# moveWiFi.net
KiCad netlist of a schematic drawn in Altium Designer
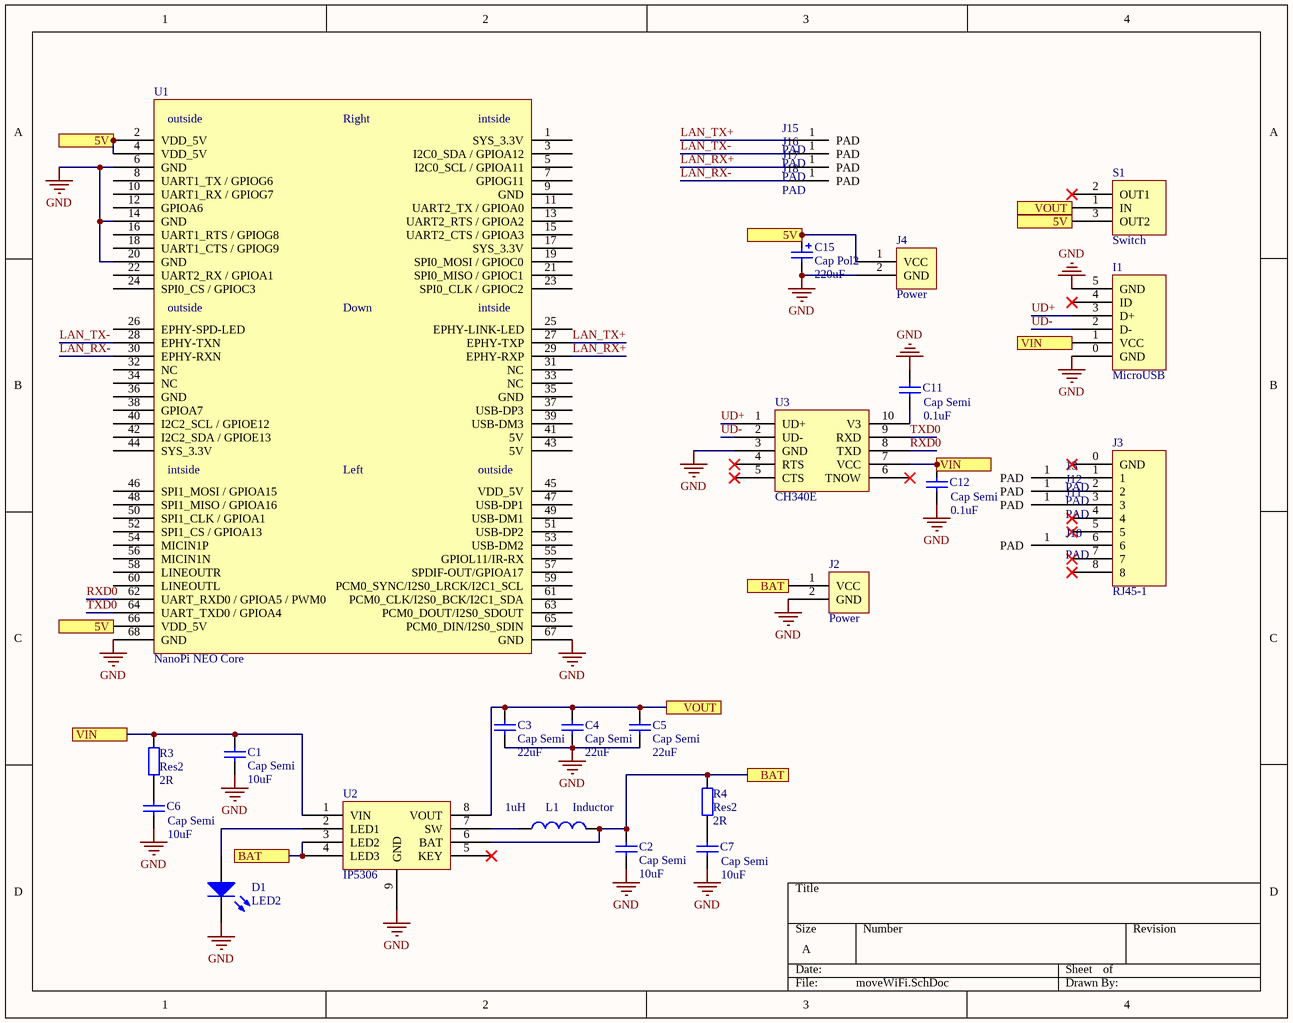
[diagram p0: moveWiFi.SchDoc]

(export (version "E")
  (design (tool "Eeschema 10.0.6"))
  (components
    (comp (ref "13") (value "PAD") (footprint "PAD") (libsource (lib "GavinPCBLib") (part "PAD")))
    (comp (ref "C1")
      (value "Cap Semi")
      (footprint "我的元件库01:C0805")
      (description "Capacitor (Semiconductor SIM Model)")
      (fields (field (name "ALTIUM_VALUE") "10uF") (field (name "PUBLISHER") "Altium Limited"))
      (libsource (lib "Miscellaneous Devices") (part "Cap Semi"))
    )
    (comp (ref "C2")
      (value "Cap Semi")
      (footprint "我的元件库01:C0805")
      (description "Capacitor (Semiconductor SIM Model)")
      (fields (field (name "ALTIUM_VALUE") "10uF") (field (name "PUBLISHER") "Altium Limited"))
      (libsource (lib "Miscellaneous Devices") (part "Cap Semi"))
    )
    (comp (ref "C3")
      (value "Cap Semi")
      (footprint "我的元件库01:C0805")
      (description "Capacitor (Semiconductor SIM Model)")
      (fields (field (name "ALTIUM_VALUE") "22uF") (field (name "PUBLISHER") "Altium Limited"))
      (libsource (lib "Miscellaneous Devices") (part "Cap Semi"))
    )
    (comp (ref "C4")
      (value "Cap Semi")
      (footprint "我的元件库01:C0805")
      (description "Capacitor (Semiconductor SIM Model)")
      (fields (field (name "ALTIUM_VALUE") "22uF") (field (name "PUBLISHER") "Altium Limited"))
      (libsource (lib "Miscellaneous Devices") (part "Cap Semi"))
    )
    (comp (ref "C5")
      (value "Cap Semi")
      (footprint "我的元件库01:C0805")
      (description "Capacitor (Semiconductor SIM Model)")
      (fields (field (name "ALTIUM_VALUE") "22uF") (field (name "PUBLISHER") "Altium Limited"))
      (libsource (lib "Miscellaneous Devices") (part "Cap Semi"))
    )
    (comp (ref "C6")
      (value "Cap Semi")
      (footprint "我的元件库01:C0805")
      (description "Capacitor (Semiconductor SIM Model)")
      (fields (field (name "ALTIUM_VALUE") "10uF") (field (name "PUBLISHER") "Altium Limited"))
      (libsource (lib "Miscellaneous Devices") (part "Cap Semi"))
    )
    (comp (ref "C7")
      (value "Cap Semi")
      (footprint "我的元件库01:C0805")
      (description "Capacitor (Semiconductor SIM Model)")
      (fields (field (name "ALTIUM_VALUE") "10uF") (field (name "PUBLISHER") "Altium Limited"))
      (libsource (lib "Miscellaneous Devices") (part "Cap Semi"))
    )
    (comp (ref "C11")
      (value "Cap Semi")
      (footprint "C0603")
      (description "Capacitor (Semiconductor SIM Model)")
      (fields (field (name "ALTIUM_VALUE") "0.1uF") (field (name "PUBLISHER") "Altium Limited"))
      (libsource (lib "Miscellaneous Devices") (part "Cap Semi"))
    )
    (comp (ref "C12")
      (value "Cap Semi")
      (footprint "C0603")
      (description "Capacitor (Semiconductor SIM Model)")
      (fields (field (name "ALTIUM_VALUE") "0.1uF") (field (name "PUBLISHER") "Altium Limited"))
      (libsource (lib "Miscellaneous Devices") (part "Cap Semi"))
    )
    (comp (ref "C15")
      (value "Cap Pol2")
      (footprint "C7343")
      (description "Polarized Capacitor (Axial)")
      (fields (field (name "ALTIUM_VALUE") "220uF") (field (name "PUBLISHER") "Altium Limited"))
      (libsource (lib "Miscellaneous Devices") (part "Cap Pol2"))
    )
    (comp (ref "D1")
      (value "LED2")
      (footprint "R0603")
      (description "Typical RED, GREEN, YELLOW, AMBER GaAs LED")
      (fields (field (name "PUBLISHER") "Altium Limited"))
      (libsource (lib "Miscellaneous Devices") (part "LED2"))
    )
    (comp (ref "I1")
      (value "MicroUSB")
      (footprint "MicroUSB")
      (libsource (lib "GavinPCBLib") (part "MicroUSB"))
    )
    (comp (ref "J2") (value "Power") (footprint "Power 2") (libsource (lib "GavinPCBLib") (part "Power")))
    (comp (ref "J3") (value "RJ45-1") (footprint "RG45-3") (libsource (lib "GavinPCBLib") (part "RJ45-3")))
    (comp (ref "J4") (value "Power") (footprint "Power 2") (libsource (lib "GavinPCBLib") (part "Power")))
    (comp (ref "J10") (value "PAD") (footprint "PAD") (libsource (lib "GavinPCBLib") (part "PAD")))
    (comp (ref "J11") (value "PAD") (footprint "PAD") (libsource (lib "GavinPCBLib") (part "PAD")))
    (comp (ref "J12") (value "PAD") (footprint "PAD") (libsource (lib "GavinPCBLib") (part "PAD")))
    (comp (ref "J15") (value "PAD") (footprint "PAD") (libsource (lib "GavinPCBLib") (part "PAD")))
    (comp (ref "J16") (value "PAD") (footprint "PAD") (libsource (lib "GavinPCBLib") (part "PAD")))
    (comp (ref "J17") (value "PAD") (footprint "PAD") (libsource (lib "GavinPCBLib") (part "PAD")))
    (comp (ref "J18") (value "PAD") (footprint "PAD") (libsource (lib "GavinPCBLib") (part "PAD")))
    (comp (ref "L1")
      (value "Inductor")
      (footprint "L0630")
      (fields (field (name "ALTIUM_VALUE") "1uH") (field (name "PUBLISHER") "Altium Limited"))
      (libsource (lib "Miscellaneous Devices") (part "Inductor"))
    )
    (comp (ref "R3")
      (value "Res2")
      (footprint "R0603")
      (description "Resistor")
      (fields (field (name "ALTIUM_VALUE") "2R") (field (name "PUBLISHER") "Altium Limited"))
      (libsource (lib "Miscellaneous Devices") (part "Res2"))
    )
    (comp (ref "R4")
      (value "Res2")
      (footprint "R0603")
      (description "Resistor")
      (fields (field (name "ALTIUM_VALUE") "2R") (field (name "PUBLISHER") "Altium Limited"))
      (libsource (lib "Miscellaneous Devices") (part "Res2"))
    )
    (comp (ref "S1") (value "Switch") (footprint "SwitchA") (libsource (lib "GavinPCBLib") (part "Switch")))
    (comp (ref "U1")
      (value "NanoPi NEO Core")
      (footprint "NanoPi_NEO_Core3")
      (libsource (lib "GavinPCBLib") (part "NanoPi_NEO_Core"))
    )
    (comp (ref "U2") (value "IP5306") (footprint "eSOP8") (libsource (lib "GavinPCBLib") (part "IP5306")))
    (comp (ref "U3") (value "CH340E") (footprint "MSOP-10") (libsource (lib "GavinPCBLib") (part "CH340E")))
  )
  (nets
    (net (code "1") (name "/5V") (class "Default")
      (node (ref "C15") (pin "1") (pinfunction "1_1") (pintype "passive"))
      (node (ref "J4") (pin "1") (pinfunction "VCC_1") (pintype "passive"))
      (node (ref "S1") (pin "3") (pinfunction "OUT2_3") (pintype "passive"))
      (node (ref "U1") (pin "2") (pinfunction "VDD_5V_2") (pintype "passive"))
      (node (ref "U1") (pin "4") (pinfunction "VDD_5V_4") (pintype "passive"))
      (node (ref "U1") (pin "66") (pinfunction "VDD_5V_66") (pintype "passive"))
    )
    (net (code "2") (name "/BAT") (class "Default")
      (node (ref "C2") (pin "2") (pinfunction "2_2") (pintype "passive"))
      (node (ref "J2") (pin "1") (pinfunction "VCC_1") (pintype "passive"))
      (node (ref "L1") (pin "2") (pinfunction "2_2") (pintype "passive"))
      (node (ref "R4") (pin "2") (pinfunction "2_2") (pintype "passive"))
      (node (ref "U2") (pin "3") (pinfunction "LED2_3") (pintype "passive"))
      (node (ref "U2") (pin "4") (pinfunction "LED3_4") (pintype "passive"))
      (node (ref "U2") (pin "6") (pinfunction "BAT_6") (pintype "passive"))
    )
    (net (code "3") (name "/LAN_RX+") (class "Default")
      (node (ref "J17") (pin "1") (pinfunction "PAD_1") (pintype "passive"))
      (node (ref "U1") (pin "29") (pinfunction "EPHY-RXP_29") (pintype "passive"))
    )
    (net (code "4") (name "/LAN_RX-") (class "Default")
      (node (ref "J18") (pin "1") (pinfunction "PAD_1") (pintype "passive"))
      (node (ref "U1") (pin "30") (pinfunction "EPHY-RXN_30") (pintype "passive"))
    )
    (net (code "5") (name "/LAN_TX+") (class "Default")
      (node (ref "J15") (pin "1") (pinfunction "PAD_1") (pintype "passive"))
      (node (ref "U1") (pin "27") (pinfunction "EPHY-TXP_27") (pintype "passive"))
    )
    (net (code "6") (name "/LAN_TX-") (class "Default")
      (node (ref "J16") (pin "1") (pinfunction "PAD_1") (pintype "passive"))
      (node (ref "U1") (pin "28") (pinfunction "EPHY-TXN_28") (pintype "passive"))
    )
    (net (code "7") (name "/RXD0") (class "Default")
      (node (ref "U1") (pin "62") (pinfunction "UART_RXD0_/_GPIOA5_/_PWM0_62") (pintype "passive"))
      (node (ref "U3") (pin "8") (pinfunction "TXD_8") (pintype "passive"))
    )
    (net (code "8") (name "/TXD0") (class "Default")
      (node (ref "U1") (pin "64") (pinfunction "UART_TXD0_/_GPIOA4_64") (pintype "passive"))
      (node (ref "U3") (pin "9") (pinfunction "RXD_9") (pintype "passive"))
    )
    (net (code "9") (name "/UD+") (class "Default")
      (node (ref "I1") (pin "3") (pinfunction "D+_3") (pintype "passive"))
      (node (ref "U3") (pin "1") (pinfunction "UD+_1") (pintype "passive"))
    )
    (net (code "10") (name "/UD-") (class "Default")
      (node (ref "I1") (pin "2") (pinfunction "D-_2") (pintype "passive"))
      (node (ref "U3") (pin "2") (pinfunction "UD-_2") (pintype "passive"))
    )
    (net (code "11") (name "/VIN") (class "Default")
      (node (ref "C1") (pin "2") (pinfunction "2_2") (pintype "passive"))
      (node (ref "C12") (pin "2") (pinfunction "2_2") (pintype "passive"))
      (node (ref "I1") (pin "1") (pinfunction "VCC_1") (pintype "passive"))
      (node (ref "R3") (pin "2") (pinfunction "2_2") (pintype "passive"))
      (node (ref "U2") (pin "1") (pinfunction "VIN_1") (pintype "passive"))
      (node (ref "U3") (pin "7") (pinfunction "VCC_7") (pintype "passive"))
    )
    (net (code "12") (name "/VOUT") (class "Default")
      (node (ref "C3") (pin "2") (pinfunction "2_2") (pintype "passive"))
      (node (ref "C4") (pin "2") (pinfunction "2_2") (pintype "passive"))
      (node (ref "C5") (pin "2") (pinfunction "2_2") (pintype "passive"))
      (node (ref "S1") (pin "1") (pinfunction "IN_1") (pintype "passive"))
      (node (ref "U2") (pin "8") (pinfunction "VOUT_8") (pintype "passive"))
    )
    (net (code "13") (name "GND") (class "Default")
      (node (ref "C1") (pin "1") (pinfunction "1_1") (pintype "passive"))
      (node (ref "C11") (pin "2") (pinfunction "2_2") (pintype "passive"))
      (node (ref "C12") (pin "1") (pinfunction "1_1") (pintype "passive"))
      (node (ref "C15") (pin "2") (pinfunction "2_2") (pintype "passive"))
      (node (ref "C2") (pin "1") (pinfunction "1_1") (pintype "passive"))
      (node (ref "C3") (pin "1") (pinfunction "1_1") (pintype "passive"))
      (node (ref "C4") (pin "1") (pinfunction "1_1") (pintype "passive"))
      (node (ref "C5") (pin "1") (pinfunction "1_1") (pintype "passive"))
      (node (ref "C6") (pin "1") (pinfunction "1_1") (pintype "passive"))
      (node (ref "C7") (pin "1") (pinfunction "1_1") (pintype "passive"))
      (node (ref "D1") (pin "2") (pinfunction "K_2") (pintype "passive"))
      (node (ref "I1") (pin "0") (pinfunction "GND_0") (pintype "passive"))
      (node (ref "I1") (pin "5") (pinfunction "GND_5") (pintype "passive"))
      (node (ref "J2") (pin "2") (pinfunction "GND_2") (pintype "passive"))
      (node (ref "J4") (pin "2") (pinfunction "GND_2") (pintype "passive"))
      (node (ref "U1") (pin "14") (pinfunction "GND_14") (pintype "passive"))
      (node (ref "U1") (pin "20") (pinfunction "GND_20") (pintype "passive"))
      (node (ref "U1") (pin "6") (pinfunction "GND_6") (pintype "passive"))
      (node (ref "U1") (pin "67") (pinfunction "GND_67") (pintype "passive"))
      (node (ref "U1") (pin "68") (pinfunction "GND_68") (pintype "passive"))
      (node (ref "U2") (pin "9") (pinfunction "GND_9") (pintype "passive"))
      (node (ref "U3") (pin "3") (pinfunction "GND_3") (pintype "passive"))
    )
    (net (code "14") (name "Net-(13-PAD)") (class "Default")
      (node (ref "13") (pin "1") (pinfunction "PAD_1") (pintype "passive"))
      (node (ref "J3") (pin "1") (pinfunction "1_1") (pintype "passive"))
    )
    (net (code "15") (name "Net-(C6-Pad2)") (class "Default")
      (node (ref "C6") (pin "2") (pinfunction "2_2") (pintype "passive"))
      (node (ref "R3") (pin "1") (pinfunction "1_1") (pintype "passive"))
    )
    (net (code "16") (name "Net-(C7-Pad2)") (class "Default")
      (node (ref "C7") (pin "2") (pinfunction "2_2") (pintype "passive"))
      (node (ref "R4") (pin "1") (pinfunction "1_1") (pintype "passive"))
    )
    (net (code "17") (name "Net-(D1-A)") (class "Default")
      (node (ref "D1") (pin "1") (pinfunction "A_1") (pintype "passive"))
      (node (ref "U2") (pin "2") (pinfunction "LED1_2") (pintype "passive"))
    )
    (net (code "18") (name "Net-(J10-PAD)") (class "Default")
      (node (ref "J10") (pin "1") (pinfunction "PAD_1") (pintype "passive"))
      (node (ref "J3") (pin "6") (pinfunction "6_6") (pintype "passive"))
    )
    (net (code "19") (name "Net-(J11-PAD)") (class "Default")
      (node (ref "J11") (pin "1") (pinfunction "PAD_1") (pintype "passive"))
      (node (ref "J3") (pin "3") (pinfunction "3_3") (pintype "passive"))
    )
    (net (code "20") (name "Net-(J12-PAD)") (class "Default")
      (node (ref "J12") (pin "1") (pinfunction "PAD_1") (pintype "passive"))
      (node (ref "J3") (pin "2") (pinfunction "2_2") (pintype "passive"))
    )
    (net (code "21") (name "Net-(U2-SW)") (class "Default")
      (node (ref "L1") (pin "1") (pinfunction "1_1") (pintype "passive"))
      (node (ref "U2") (pin "7") (pinfunction "SW_7") (pintype "passive"))
    )
    (net (code "22") (name "Net-(U3-V3)") (class "Default")
      (node (ref "C11") (pin "1") (pinfunction "1_1") (pintype "passive"))
      (node (ref "U3") (pin "10") (pinfunction "V3_10") (pintype "passive"))
    )
    (net (code "23") (name "unconnected-(I1-ID-Pad4)") (class "Default")
      (node (ref "I1") (pin "4") (pinfunction "ID_4") (pintype "passive+no_connect"))
    )
    (net (code "24") (name "unconnected-(J3-GND-Pad0)") (class "Default")
      (node (ref "J3") (pin "0") (pinfunction "GND_0") (pintype "passive+no_connect"))
    )
    (net (code "25") (name "unconnected-(J3-Pad4)") (class "Default")
      (node (ref "J3") (pin "4") (pinfunction "4_4") (pintype "passive+no_connect"))
    )
    (net (code "26") (name "unconnected-(J3-Pad5)") (class "Default")
      (node (ref "J3") (pin "5") (pinfunction "5_5") (pintype "passive+no_connect"))
    )
    (net (code "27") (name "unconnected-(J3-Pad7)") (class "Default")
      (node (ref "J3") (pin "7") (pinfunction "7_7") (pintype "passive+no_connect"))
    )
    (net (code "28") (name "unconnected-(J3-Pad8)") (class "Default")
      (node (ref "J3") (pin "8") (pinfunction "8_8") (pintype "passive+no_connect"))
    )
    (net (code "29") (name "unconnected-(S1-OUT1-Pad2)") (class "Default")
      (node (ref "S1") (pin "2") (pinfunction "OUT1_2") (pintype "passive+no_connect"))
    )
    (net (code "30") (name "unconnected-(U1-5V-Pad41)") (class "Default")
      (node (ref "U1") (pin "41") (pinfunction "5V_41") (pintype "passive"))
    )
    (net (code "31") (name "unconnected-(U1-5V-Pad43)") (class "Default")
      (node (ref "U1") (pin "43") (pinfunction "5V_43") (pintype "passive"))
    )
    (net (code "32") (name "unconnected-(U1-EPHY-LINK-LED-Pad25)") (class "Default")
      (node (ref "U1") (pin "25") (pinfunction "EPHY-LINK-LED_25") (pintype "passive"))
    )
    (net (code "33") (name "unconnected-(U1-EPHY-SPD-LED-Pad26)") (class "Default")
      (node (ref "U1") (pin "26") (pinfunction "EPHY-SPD-LED_26") (pintype "passive"))
    )
    (net (code "34") (name "unconnected-(U1-GND-Pad9)") (class "Default")
      (node (ref "U1") (pin "9") (pinfunction "GND_9") (pintype "passive"))
    )
    (net (code "35") (name "unconnected-(U1-GND-Pad35)") (class "Default")
      (node (ref "U1") (pin "35") (pinfunction "GND_35") (pintype "passive"))
    )
    (net (code "36") (name "unconnected-(U1-GND-Pad36)") (class "Default")
      (node (ref "U1") (pin "36") (pinfunction "GND_36") (pintype "passive"))
    )
    (net (code "37") (name "unconnected-(U1-GPIOA6-Pad12)") (class "Default")
      (node (ref "U1") (pin "12") (pinfunction "GPIOA6_12") (pintype "passive"))
    )
    (net (code "38") (name "unconnected-(U1-GPIOA7-Pad38)") (class "Default")
      (node (ref "U1") (pin "38") (pinfunction "GPIOA7_38") (pintype "passive"))
    )
    (net (code "39") (name "unconnected-(U1-GPIOG11-Pad7)") (class "Default")
      (node (ref "U1") (pin "7") (pinfunction "GPIOG11_7") (pintype "passive"))
    )
    (net (code "40") (name "unconnected-(U1-GPIOL11{slash}IR-RX-Pad55)") (class "Default")
      (node (ref "U1") (pin "55") (pinfunction "GPIOL11/IR-RX_55") (pintype "passive"))
    )
    (net (code "41") (name "unconnected-(U1-I2C0_SCL_{slash}_GPIOA11-Pad5)") (class "Default")
      (node (ref "U1") (pin "5") (pinfunction "I2C0_SCL_/_GPIOA11_5") (pintype "passive"))
    )
    (net (code "42") (name "unconnected-(U1-I2C0_SDA_{slash}_GPIOA12-Pad3)") (class "Default")
      (node (ref "U1") (pin "3") (pinfunction "I2C0_SDA_/_GPIOA12_3") (pintype "passive"))
    )
    (net (code "43") (name "unconnected-(U1-I2C2_SCL_{slash}_GPIOE12-Pad40)") (class "Default")
      (node (ref "U1") (pin "40") (pinfunction "I2C2_SCL_/_GPIOE12_40") (pintype "passive"))
    )
    (net (code "44") (name "unconnected-(U1-I2C2_SDA_{slash}_GPIOE13-Pad42)") (class "Default")
      (node (ref "U1") (pin "42") (pinfunction "I2C2_SDA_/_GPIOE13_42") (pintype "passive"))
    )
    (net (code "45") (name "unconnected-(U1-LINEOUTL-Pad60)") (class "Default")
      (node (ref "U1") (pin "60") (pinfunction "LINEOUTL_60") (pintype "passive"))
    )
    (net (code "46") (name "unconnected-(U1-LINEOUTR-Pad58)") (class "Default")
      (node (ref "U1") (pin "58") (pinfunction "LINEOUTR_58") (pintype "passive"))
    )
    (net (code "47") (name "unconnected-(U1-MICIN1N-Pad56)") (class "Default")
      (node (ref "U1") (pin "56") (pinfunction "MICIN1N_56") (pintype "passive"))
    )
    (net (code "48") (name "unconnected-(U1-MICIN1P-Pad54)") (class "Default")
      (node (ref "U1") (pin "54") (pinfunction "MICIN1P_54") (pintype "passive"))
    )
    (net (code "49") (name "unconnected-(U1-NC-Pad31)") (class "Default")
      (node (ref "U1") (pin "31") (pinfunction "NC_31") (pintype "passive"))
    )
    (net (code "50") (name "unconnected-(U1-NC-Pad32)") (class "Default")
      (node (ref "U1") (pin "32") (pinfunction "NC_32") (pintype "passive"))
    )
    (net (code "51") (name "unconnected-(U1-NC-Pad33)") (class "Default")
      (node (ref "U1") (pin "33") (pinfunction "NC_33") (pintype "passive"))
    )
    (net (code "52") (name "unconnected-(U1-NC-Pad34)") (class "Default")
      (node (ref "U1") (pin "34") (pinfunction "NC_34") (pintype "passive"))
    )
    (net (code "53") (name "unconnected-(U1-PCM0_CLK{slash}I2S0_BCK{slash}I2C1_SDA-Pad61)") (class "Default")
      (node (ref "U1") (pin "61") (pinfunction "PCM0_CLK/I2S0_BCK/I2C1_SDA_61") (pintype "passive"))
    )
    (net (code "54") (name "unconnected-(U1-PCM0_DIN{slash}I2S0_SDIN-Pad65)") (class "Default")
      (node (ref "U1") (pin "65") (pinfunction "PCM0_DIN/I2S0_SDIN_65") (pintype "passive"))
    )
    (net (code "55") (name "unconnected-(U1-PCM0_DOUT{slash}I2S0_SDOUT-Pad63)") (class "Default")
      (node (ref "U1") (pin "63") (pinfunction "PCM0_DOUT/I2S0_SDOUT_63") (pintype "passive"))
    )
    (net (code "56") (name "unconnected-(U1-PCM0_SYNC{slash}I2S0_LRCK{slash}I2C1_SCL-Pad59)") (class "Default")
      (node (ref "U1") (pin "59") (pinfunction "PCM0_SYNC/I2S0_LRCK/I2C1_SCL_59") (pintype "passive"))
    )
    (net (code "57") (name "unconnected-(U1-SPDIF-OUT{slash}GPIOA17-Pad57)") (class "Default")
      (node (ref "U1") (pin "57") (pinfunction "SPDIF-OUT/GPIOA17_57") (pintype "passive"))
    )
    (net (code "58") (name "unconnected-(U1-SPI0_CLK_{slash}_GPIOC2-Pad23)") (class "Default")
      (node (ref "U1") (pin "23") (pinfunction "SPI0_CLK_/_GPIOC2_23") (pintype "passive"))
    )
    (net (code "59") (name "unconnected-(U1-SPI0_CS_{slash}_GPIOC3-Pad24)") (class "Default")
      (node (ref "U1") (pin "24") (pinfunction "SPI0_CS_/_GPIOC3_24") (pintype "passive"))
    )
    (net (code "60") (name "unconnected-(U1-SPI0_MISO_{slash}_GPIOC1-Pad21)") (class "Default")
      (node (ref "U1") (pin "21") (pinfunction "SPI0_MISO_/_GPIOC1_21") (pintype "passive"))
    )
    (net (code "61") (name "unconnected-(U1-SPI0_MOSI_{slash}_GPIOC0-Pad19)") (class "Default")
      (node (ref "U1") (pin "19") (pinfunction "SPI0_MOSI_/_GPIOC0_19") (pintype "passive"))
    )
    (net (code "62") (name "unconnected-(U1-SPI1_CLK_{slash}_GPIOA1-Pad50)") (class "Default")
      (node (ref "U1") (pin "50") (pinfunction "SPI1_CLK_/_GPIOA1_50") (pintype "passive"))
    )
    (net (code "63") (name "unconnected-(U1-SPI1_CS_{slash}_GPIOA13-Pad52)") (class "Default")
      (node (ref "U1") (pin "52") (pinfunction "SPI1_CS_/_GPIOA13_52") (pintype "passive"))
    )
    (net (code "64") (name "unconnected-(U1-SPI1_MISO_{slash}_GPIOA16-Pad48)") (class "Default")
      (node (ref "U1") (pin "48") (pinfunction "SPI1_MISO_/_GPIOA16_48") (pintype "passive"))
    )
    (net (code "65") (name "unconnected-(U1-SPI1_MOSI_{slash}_GPIOA15-Pad46)") (class "Default")
      (node (ref "U1") (pin "46") (pinfunction "SPI1_MOSI_/_GPIOA15_46") (pintype "passive"))
    )
    (net (code "66") (name "unconnected-(U1-SYS_3.3V-Pad1)") (class "Default")
      (node (ref "U1") (pin "1") (pinfunction "SYS_3.3V_1") (pintype "passive"))
    )
    (net (code "67") (name "unconnected-(U1-SYS_3.3V-Pad17)") (class "Default")
      (node (ref "U1") (pin "17") (pinfunction "SYS_3.3V_17") (pintype "passive"))
    )
    (net (code "68") (name "unconnected-(U1-SYS_3.3V-Pad44)") (class "Default")
      (node (ref "U1") (pin "44") (pinfunction "SYS_3.3V_44") (pintype "passive"))
    )
    (net (code "69") (name "unconnected-(U1-UART1_CTS_{slash}_GPIOG9-Pad18)") (class "Default")
      (node (ref "U1") (pin "18") (pinfunction "UART1_CTS_/_GPIOG9_18") (pintype "passive"))
    )
    (net (code "70") (name "unconnected-(U1-UART1_RTS_{slash}_GPIOG8-Pad16)") (class "Default")
      (node (ref "U1") (pin "16") (pinfunction "UART1_RTS_/_GPIOG8_16") (pintype "passive"))
    )
    (net (code "71") (name "unconnected-(U1-UART1_RX_{slash}_GPIOG7-Pad10)") (class "Default")
      (node (ref "U1") (pin "10") (pinfunction "UART1_RX_/_GPIOG7_10") (pintype "passive"))
    )
    (net (code "72") (name "unconnected-(U1-UART1_TX_{slash}_GPIOG6-Pad8)") (class "Default")
      (node (ref "U1") (pin "8") (pinfunction "UART1_TX_/_GPIOG6_8") (pintype "passive"))
    )
    (net (code "73") (name "unconnected-(U1-UART2_CTS_{slash}_GPIOA3-Pad15)") (class "Default")
      (node (ref "U1") (pin "15") (pinfunction "UART2_CTS_/_GPIOA3_15") (pintype "passive"))
    )
    (net (code "74") (name "unconnected-(U1-UART2_RTS_{slash}_GPIOA2-Pad13)") (class "Default")
      (node (ref "U1") (pin "13") (pinfunction "UART2_RTS_/_GPIOA2_13") (pintype "passive"))
    )
    (net (code "75") (name "unconnected-(U1-UART2_RX_{slash}_GPIOA1-Pad22)") (class "Default")
      (node (ref "U1") (pin "22") (pinfunction "UART2_RX_/_GPIOA1_22") (pintype "passive"))
    )
    (net (code "76") (name "unconnected-(U1-UART2_TX_{slash}_GPIOA0-Pad11)") (class "Default")
      (node (ref "U1") (pin "11") (pinfunction "UART2_TX_/_GPIOA0_11") (pintype "passive"))
    )
    (net (code "77") (name "unconnected-(U1-USB-DM1-Pad49)") (class "Default")
      (node (ref "U1") (pin "49") (pinfunction "USB-DM1_49") (pintype "passive"))
    )
    (net (code "78") (name "unconnected-(U1-USB-DM2-Pad53)") (class "Default")
      (node (ref "U1") (pin "53") (pinfunction "USB-DM2_53") (pintype "passive"))
    )
    (net (code "79") (name "unconnected-(U1-USB-DM3-Pad39)") (class "Default")
      (node (ref "U1") (pin "39") (pinfunction "USB-DM3_39") (pintype "passive"))
    )
    (net (code "80") (name "unconnected-(U1-USB-DP1-Pad47)") (class "Default")
      (node (ref "U1") (pin "47") (pinfunction "USB-DP1_47") (pintype "passive"))
    )
    (net (code "81") (name "unconnected-(U1-USB-DP2-Pad51)") (class "Default")
      (node (ref "U1") (pin "51") (pinfunction "USB-DP2_51") (pintype "passive"))
    )
    (net (code "82") (name "unconnected-(U1-USB-DP3-Pad37)") (class "Default")
      (node (ref "U1") (pin "37") (pinfunction "USB-DP3_37") (pintype "passive"))
    )
    (net (code "83") (name "unconnected-(U1-VDD_5V-Pad45)") (class "Default")
      (node (ref "U1") (pin "45") (pinfunction "VDD_5V_45") (pintype "passive"))
    )
    (net (code "84") (name "unconnected-(U2-KEY-Pad5)") (class "Default")
      (node (ref "U2") (pin "5") (pinfunction "KEY_5") (pintype "passive+no_connect"))
    )
    (net (code "85") (name "unconnected-(U3-CTS-Pad5)") (class "Default")
      (node (ref "U3") (pin "5") (pinfunction "CTS_5") (pintype "passive+no_connect"))
    )
    (net (code "86") (name "unconnected-(U3-RTS-Pad4)") (class "Default")
      (node (ref "U3") (pin "4") (pinfunction "RTS_4") (pintype "passive+no_connect"))
    )
    (net (code "87") (name "unconnected-(U3-TNOW-Pad6)") (class "Default")
      (node (ref "U3") (pin "6") (pinfunction "TNOW_6") (pintype "passive+no_connect"))
    )
  )
)
